# Scheme.net
KiCad netlist of a schematic drawn in Altium Designer
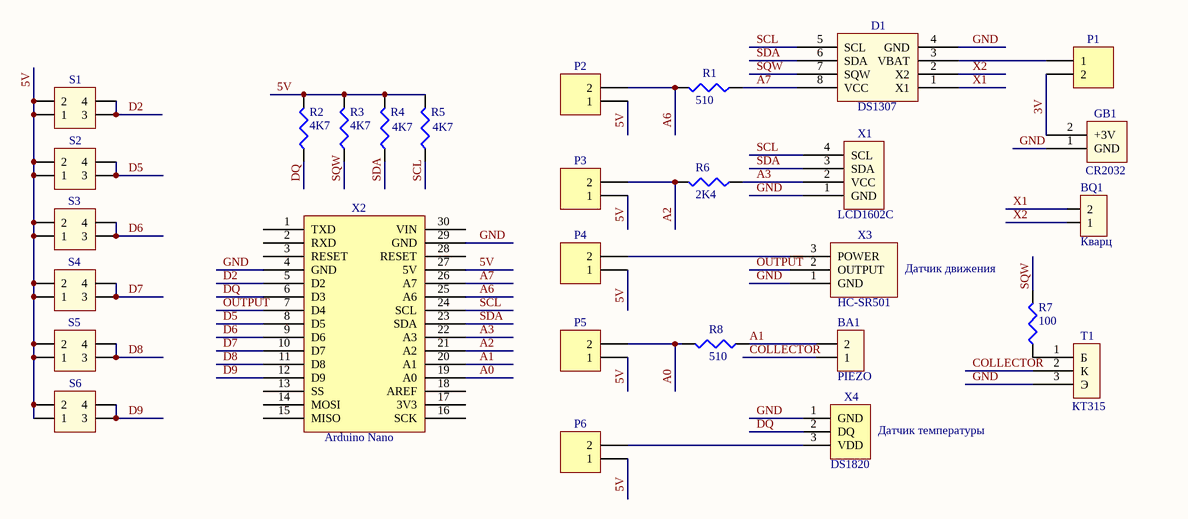
[diagram p0: Scheme.SchDoc]

(export (version "E")
  (design (tool "Eeschema 10.0.6"))
  (components
    (comp (ref "BA1")
      (value "PIEZO")
      (footprint "Piezo Buzzer")
      (libsource (lib "Schlib_KGB") (part "PIEZO"))
    )
    (comp (ref "BQ1") (value "DT-38") (footprint "DT-38") (libsource (lib "Schlib_KGB") (part "DT-38")))
    (comp (ref "D1")
      (value "DS1307")
      (footprint "PcbLib_KGB:DS1307")
      (libsource (lib "Schlib_KGB") (part "DS1307"))
    )
    (comp (ref "GB1")
      (value "CR2032")
      (footprint "BAT CR2032 3V")
      (libsource (lib "Schlib_KGB") (part "BAT CR2032 3V"))
    )
    (comp (ref "P1")
      (value "Header 2")
      (footprint "HDR1X2")
      (description "Header, 2-Pin")
      (fields (field (name "PUBLISHER") "Altium Limited"))
      (libsource (lib "Miscellaneous Connectors") (part "Header 2"))
    )
    (comp (ref "P2")
      (value "Header 2")
      (footprint "HDR1X2")
      (description "Header, 2-Pin")
      (fields (field (name "PUBLISHER") "Altium Limited"))
      (libsource (lib "") (part "Header 2_1"))
    )
    (comp (ref "P3")
      (value "Header 2")
      (footprint "HDR1X2")
      (description "Header, 2-Pin")
      (fields (field (name "PUBLISHER") "Altium Limited"))
      (libsource (lib "") (part "Header 2_1"))
    )
    (comp (ref "P4")
      (value "Header 2")
      (footprint "HDR1X2")
      (description "Header, 2-Pin")
      (fields (field (name "PUBLISHER") "Altium Limited"))
      (libsource (lib "") (part "Header 2_1"))
    )
    (comp (ref "P5")
      (value "Header 2")
      (footprint "HDR1X2")
      (description "Header, 2-Pin")
      (fields (field (name "PUBLISHER") "Altium Limited"))
      (libsource (lib "") (part "Header 2_1"))
    )
    (comp (ref "P6")
      (value "Header 2")
      (footprint "HDR1X2")
      (description "Header, 2-Pin")
      (fields (field (name "PUBLISHER") "Altium Limited"))
      (libsource (lib "") (part "Header 2_1"))
    )
    (comp (ref "R1")
      (value "510")
      (footprint "J1-0603")
      (description "Resistor")
      (fields (field (name "PUBLISHER") "Altium Limited"))
      (libsource (lib "Miscellaneous Devices") (part "Res3"))
    )
    (comp (ref "R2")
      (value "4K7")
      (footprint "J1-0603")
      (description "Resistor")
      (fields (field (name "PUBLISHER") "Altium Limited"))
      (libsource (lib "Miscellaneous Devices") (part "Res3"))
    )
    (comp (ref "R3")
      (value "4K7")
      (footprint "J1-0603")
      (description "Resistor")
      (fields (field (name "PUBLISHER") "Altium Limited"))
      (libsource (lib "Miscellaneous Devices") (part "Res3"))
    )
    (comp (ref "R4")
      (value "4K7")
      (footprint "J1-0603")
      (description "Resistor")
      (fields (field (name "PUBLISHER") "Altium Limited"))
      (libsource (lib "Miscellaneous Devices") (part "Res3"))
    )
    (comp (ref "R5")
      (value "4K7")
      (footprint "J1-0603")
      (description "Resistor")
      (fields (field (name "PUBLISHER") "Altium Limited"))
      (libsource (lib "Miscellaneous Devices") (part "Res3"))
    )
    (comp (ref "R6")
      (value "2K4")
      (footprint "J1-0603")
      (description "Resistor")
      (fields (field (name "PUBLISHER") "Altium Limited"))
      (libsource (lib "Miscellaneous Devices") (part "Res3"))
    )
    (comp (ref "R7")
      (value "100")
      (footprint "J1-0603")
      (description "Resistor")
      (fields (field (name "PUBLISHER") "Altium Limited"))
      (libsource (lib "Miscellaneous Devices") (part "Res3"))
    )
    (comp (ref "R8")
      (value "510")
      (footprint "J1-0603")
      (description "Resistor")
      (fields (field (name "PUBLISHER") "Altium Limited"))
      (libsource (lib "Miscellaneous Devices") (part "Res3"))
    )
    (comp (ref "S1")
      (value "12X12 mm BUTTON")
      (footprint "12X12mm BUTTON")
      (libsource (lib "Schlib_KGB") (part "12X12 mm BUTTON"))
    )
    (comp (ref "S2")
      (value "12X12 mm BUTTON")
      (footprint "12X12mm BUTTON")
      (libsource (lib "Schlib_KGB") (part "12X12 mm BUTTON"))
    )
    (comp (ref "S3")
      (value "12X12 mm BUTTON")
      (footprint "12X12mm BUTTON")
      (libsource (lib "Schlib_KGB") (part "12X12 mm BUTTON"))
    )
    (comp (ref "S4")
      (value "12X12 mm BUTTON")
      (footprint "12X12mm BUTTON")
      (libsource (lib "Schlib_KGB") (part "12X12 mm BUTTON"))
    )
    (comp (ref "S5")
      (value "12X12 mm BUTTON")
      (footprint "12X12mm BUTTON")
      (libsource (lib "Schlib_KGB") (part "12X12 mm BUTTON"))
    )
    (comp (ref "S6")
      (value "12X12 mm BUTTON")
      (footprint "12X12mm BUTTON")
      (libsource (lib "Schlib_KGB") (part "12X12 mm BUTTON"))
    )
    (comp (ref "T1") (value "КТ315") (footprint "KT315") (libsource (lib "Schlib_KGB") (part "KT315")))
    (comp (ref "X1")
      (value "LCD1602C")
      (footprint "LCD1602")
      (libsource (lib "Schlib_KGB") (part "LCD1602C"))
    )
    (comp (ref "X2")
      (value "Arduino Nano")
      (footprint "Arduino Nano")
      (libsource (lib "Schlib_KGB") (part "Arduino Nano"))
    )
    (comp (ref "X3")
      (value "HC-SR501")
      (footprint "HC-SR501")
      (libsource (lib "Schlib_KGB") (part "HC-SR501"))
    )
    (comp (ref "X4") (value "DS1820") (footprint "DS1820") (libsource (lib "Schlib_KGB") (part "DS1820")))
  )
  (nets
    (net (code "1") (name "/3V") (class "Default")
      (node (ref "GB1") (pin "2") (pinfunction "+3V_2") (pintype "passive"))
      (node (ref "P1") (pin "2") (pinfunction "2_2") (pintype "passive"))
    )
    (net (code "2") (name "/5V") (class "Default")
      (node (ref "P2") (pin "1") (pinfunction "1_1") (pintype "passive"))
      (node (ref "P3") (pin "1") (pinfunction "1_1") (pintype "passive"))
      (node (ref "P4") (pin "1") (pinfunction "1_1") (pintype "passive"))
      (node (ref "P5") (pin "1") (pinfunction "1_1") (pintype "passive"))
      (node (ref "P6") (pin "1") (pinfunction "1_1") (pintype "passive"))
      (node (ref "R2") (pin "2") (pinfunction "2_2") (pintype "passive"))
      (node (ref "R3") (pin "2") (pinfunction "2_2") (pintype "passive"))
      (node (ref "R4") (pin "2") (pinfunction "2_2") (pintype "passive"))
      (node (ref "R5") (pin "2") (pinfunction "2_2") (pintype "passive"))
      (node (ref "S1") (pin "1") (pinfunction "1_1") (pintype "passive"))
      (node (ref "S1") (pin "2") (pinfunction "2_2") (pintype "passive"))
      (node (ref "S2") (pin "1") (pinfunction "1_1") (pintype "passive"))
      (node (ref "S2") (pin "2") (pinfunction "2_2") (pintype "passive"))
      (node (ref "S3") (pin "1") (pinfunction "1_1") (pintype "passive"))
      (node (ref "S3") (pin "2") (pinfunction "2_2") (pintype "passive"))
      (node (ref "S4") (pin "1") (pinfunction "1_1") (pintype "passive"))
      (node (ref "S4") (pin "2") (pinfunction "2_2") (pintype "passive"))
      (node (ref "S5") (pin "1") (pinfunction "1_1") (pintype "passive"))
      (node (ref "S5") (pin "2") (pinfunction "2_2") (pintype "passive"))
      (node (ref "S6") (pin "1") (pinfunction "1_1") (pintype "passive"))
      (node (ref "S6") (pin "2") (pinfunction "2_2") (pintype "passive"))
      (node (ref "X2") (pin "27") (pinfunction "5V_27") (pintype "passive"))
    )
    (net (code "3") (name "/A0") (class "Default")
      (node (ref "P5") (pin "2") (pinfunction "2_2") (pintype "passive"))
      (node (ref "R8") (pin "2") (pinfunction "2_2") (pintype "passive"))
      (node (ref "X2") (pin "19") (pinfunction "A0_19") (pintype "passive"))
    )
    (net (code "4") (name "/A1") (class "Default")
      (node (ref "BA1") (pin "2") (pinfunction "2_2") (pintype "passive"))
      (node (ref "R8") (pin "1") (pinfunction "1_1") (pintype "passive"))
      (node (ref "X2") (pin "20") (pinfunction "A1_20") (pintype "passive"))
    )
    (net (code "5") (name "/A2") (class "Default")
      (node (ref "P3") (pin "2") (pinfunction "2_2") (pintype "passive"))
      (node (ref "R6") (pin "2") (pinfunction "2_2") (pintype "passive"))
      (node (ref "X2") (pin "21") (pinfunction "A2_21") (pintype "passive"))
    )
    (net (code "6") (name "/A3") (class "Default")
      (node (ref "R6") (pin "1") (pinfunction "1_1") (pintype "passive"))
      (node (ref "X1") (pin "2") (pinfunction "VCC_2") (pintype "passive"))
      (node (ref "X2") (pin "22") (pinfunction "A3_22") (pintype "passive"))
    )
    (net (code "7") (name "/A6") (class "Default")
      (node (ref "P2") (pin "2") (pinfunction "2_2") (pintype "passive"))
      (node (ref "R1") (pin "2") (pinfunction "2_2") (pintype "passive"))
      (node (ref "X2") (pin "25") (pinfunction "A6_25") (pintype "passive"))
    )
    (net (code "8") (name "/A7") (class "Default")
      (node (ref "D1") (pin "8") (pinfunction "VCC_8") (pintype "passive"))
      (node (ref "R1") (pin "1") (pinfunction "1_1") (pintype "passive"))
      (node (ref "X2") (pin "26") (pinfunction "A7_26") (pintype "passive"))
    )
    (net (code "9") (name "/COLLECTOR") (class "Default")
      (node (ref "BA1") (pin "1") (pinfunction "1_1") (pintype "passive"))
      (node (ref "T1") (pin "2") (pinfunction "К_2") (pintype "passive"))
    )
    (net (code "10") (name "/D2") (class "Default")
      (node (ref "S1") (pin "3") (pinfunction "3_3") (pintype "passive"))
      (node (ref "S1") (pin "4") (pinfunction "4_4") (pintype "passive"))
      (node (ref "X2") (pin "5") (pinfunction "D2_5") (pintype "passive"))
    )
    (net (code "11") (name "/D5") (class "Default")
      (node (ref "S2") (pin "3") (pinfunction "3_3") (pintype "passive"))
      (node (ref "S2") (pin "4") (pinfunction "4_4") (pintype "passive"))
      (node (ref "X2") (pin "8") (pinfunction "D5_8") (pintype "passive"))
    )
    (net (code "12") (name "/D6") (class "Default")
      (node (ref "S3") (pin "3") (pinfunction "3_3") (pintype "passive"))
      (node (ref "S3") (pin "4") (pinfunction "4_4") (pintype "passive"))
      (node (ref "X2") (pin "9") (pinfunction "D6_9") (pintype "passive"))
    )
    (net (code "13") (name "/D7") (class "Default")
      (node (ref "S4") (pin "3") (pinfunction "3_3") (pintype "passive"))
      (node (ref "S4") (pin "4") (pinfunction "4_4") (pintype "passive"))
      (node (ref "X2") (pin "10") (pinfunction "D7_10") (pintype "passive"))
    )
    (net (code "14") (name "/D8") (class "Default")
      (node (ref "S5") (pin "3") (pinfunction "3_3") (pintype "passive"))
      (node (ref "S5") (pin "4") (pinfunction "4_4") (pintype "passive"))
      (node (ref "X2") (pin "11") (pinfunction "D8_11") (pintype "passive"))
    )
    (net (code "15") (name "/D9") (class "Default")
      (node (ref "S6") (pin "3") (pinfunction "3_3") (pintype "passive"))
      (node (ref "S6") (pin "4") (pinfunction "4_4") (pintype "passive"))
      (node (ref "X2") (pin "12") (pinfunction "D9_12") (pintype "passive"))
    )
    (net (code "16") (name "/DQ") (class "Default")
      (node (ref "R2") (pin "1") (pinfunction "1_1") (pintype "passive"))
      (node (ref "X2") (pin "6") (pinfunction "D3_6") (pintype "passive"))
      (node (ref "X4") (pin "2") (pinfunction "DQ_2") (pintype "passive"))
    )
    (net (code "17") (name "/GND") (class "Default")
      (node (ref "D1") (pin "4") (pinfunction "GND_4") (pintype "passive"))
      (node (ref "GB1") (pin "1") (pinfunction "GND_1") (pintype "passive"))
      (node (ref "T1") (pin "3") (pinfunction "Э_3") (pintype "passive"))
      (node (ref "X1") (pin "1") (pinfunction "GND_1") (pintype "passive"))
      (node (ref "X2") (pin "29") (pinfunction "GND_29") (pintype "passive"))
      (node (ref "X2") (pin "4") (pinfunction "GND_4") (pintype "passive"))
      (node (ref "X3") (pin "1") (pinfunction "GND_1") (pintype "passive"))
      (node (ref "X4") (pin "1") (pinfunction "GND_1") (pintype "passive"))
    )
    (net (code "18") (name "/OUTPUT") (class "Default")
      (node (ref "X2") (pin "7") (pinfunction "D4_7") (pintype "passive"))
      (node (ref "X3") (pin "2") (pinfunction "OUTPUT_2") (pintype "passive"))
    )
    (net (code "19") (name "/SCL") (class "Default")
      (node (ref "D1") (pin "5") (pinfunction "SCL_5") (pintype "passive"))
      (node (ref "R5") (pin "1") (pinfunction "1_1") (pintype "passive"))
      (node (ref "X1") (pin "4") (pinfunction "SCL_4") (pintype "passive"))
      (node (ref "X2") (pin "24") (pinfunction "SCL_24") (pintype "passive"))
    )
    (net (code "20") (name "/SDA") (class "Default")
      (node (ref "D1") (pin "6") (pinfunction "SDA_6") (pintype "passive"))
      (node (ref "R4") (pin "1") (pinfunction "1_1") (pintype "passive"))
      (node (ref "X1") (pin "3") (pinfunction "SDA_3") (pintype "passive"))
      (node (ref "X2") (pin "23") (pinfunction "SDA_23") (pintype "passive"))
    )
    (net (code "21") (name "/SQW") (class "Default")
      (node (ref "D1") (pin "7") (pinfunction "SQW_7") (pintype "passive"))
      (node (ref "R3") (pin "1") (pinfunction "1_1") (pintype "passive"))
      (node (ref "R7") (pin "2") (pinfunction "2_2") (pintype "passive"))
    )
    (net (code "22") (name "/X1") (class "Default")
      (node (ref "BQ1") (pin "2") (pinfunction "2_2") (pintype "passive"))
      (node (ref "D1") (pin "1") (pinfunction "X1_1") (pintype "passive"))
    )
    (net (code "23") (name "/X2") (class "Default")
      (node (ref "BQ1") (pin "1") (pinfunction "1_1") (pintype "passive"))
      (node (ref "D1") (pin "2") (pinfunction "X2_2") (pintype "passive"))
    )
    (net (code "24") (name "Net-(D1-VBAT)") (class "Default")
      (node (ref "D1") (pin "3") (pinfunction "VBAT_3") (pintype "passive"))
      (node (ref "P1") (pin "1") (pinfunction "1_1") (pintype "passive"))
    )
    (net (code "25") (name "Net-(T1-Б)") (class "Default")
      (node (ref "R7") (pin "1") (pinfunction "1_1") (pintype "passive"))
      (node (ref "T1") (pin "1") (pinfunction "Б_1") (pintype "passive"))
    )
    (net (code "26") (name "Net-(X3-POWER)") (class "Default")
      (node (ref "P4") (pin "2") (pinfunction "2_2") (pintype "passive"))
      (node (ref "X3") (pin "3") (pinfunction "POWER_3") (pintype "passive"))
    )
    (net (code "27") (name "Net-(X4-VDD)") (class "Default")
      (node (ref "P6") (pin "2") (pinfunction "2_2") (pintype "passive"))
      (node (ref "X4") (pin "3") (pinfunction "VDD_3") (pintype "passive"))
    )
    (net (code "28") (name "unconnected-(X2-3V3-Pad17)") (class "Default")
      (node (ref "X2") (pin "17") (pinfunction "3V3_17") (pintype "passive"))
    )
    (net (code "29") (name "unconnected-(X2-AREF-Pad18)") (class "Default")
      (node (ref "X2") (pin "18") (pinfunction "AREF_18") (pintype "passive"))
    )
    (net (code "30") (name "unconnected-(X2-MISO-Pad15)") (class "Default")
      (node (ref "X2") (pin "15") (pinfunction "MISO_15") (pintype "passive"))
    )
    (net (code "31") (name "unconnected-(X2-MOSI-Pad14)") (class "Default")
      (node (ref "X2") (pin "14") (pinfunction "MOSI_14") (pintype "passive"))
    )
    (net (code "32") (name "unconnected-(X2-RESET-Pad3)") (class "Default")
      (node (ref "X2") (pin "3") (pinfunction "RESET_3") (pintype "passive"))
    )
    (net (code "33") (name "unconnected-(X2-RESET-Pad28)") (class "Default")
      (node (ref "X2") (pin "28") (pinfunction "RESET_28") (pintype "passive"))
    )
    (net (code "34") (name "unconnected-(X2-RXD-Pad2)") (class "Default")
      (node (ref "X2") (pin "2") (pinfunction "RXD_2") (pintype "passive"))
    )
    (net (code "35") (name "unconnected-(X2-SCK-Pad16)") (class "Default")
      (node (ref "X2") (pin "16") (pinfunction "SCK_16") (pintype "passive"))
    )
    (net (code "36") (name "unconnected-(X2-SS-Pad13)") (class "Default")
      (node (ref "X2") (pin "13") (pinfunction "SS_13") (pintype "passive"))
    )
    (net (code "37") (name "unconnected-(X2-TXD-Pad1)") (class "Default")
      (node (ref "X2") (pin "1") (pinfunction "TXD_1") (pintype "passive"))
    )
    (net (code "38") (name "unconnected-(X2-VIN-Pad30)") (class "Default")
      (node (ref "X2") (pin "30") (pinfunction "VIN_30") (pintype "passive"))
    )
  )
)
